# band_pass_filter.net
KiCad netlist of a schematic drawn in EAGLE
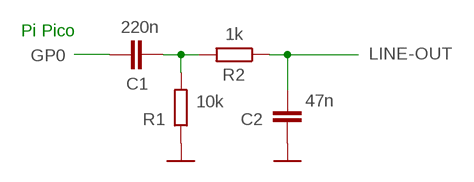
[diagram p0: schematic, sheet 1]

(export (version "E")
  (design (tool "Eeschema 10.0.6"))
  (components
    (comp (ref "C1")
      (value "220n")
      (footprint "eagle-import:C0805")
      (libsource (lib "eagle-import") (part "C"))
    )
    (comp (ref "C2")
      (value "47n")
      (footprint "eagle-import:C0805")
      (libsource (lib "eagle-import") (part "C"))
    )
    (comp (ref "R1")
      (value "10k")
      (footprint "eagle-import:R0805")
      (libsource (lib "eagle-import") (part "R"))
    )
    (comp (ref "R2")
      (value "1k")
      (footprint "eagle-import:R0805")
      (libsource (lib "eagle-import") (part "R"))
    )
  )
  (nets
    (net (code "1") (name "/GP0") (class "Default")
      (node (ref "C1") (pin "1") (pinfunction "1_1") (pintype "passive"))
    )
    (net (code "2") (name "/LINE-OUT") (class "Default")
      (node (ref "C2") (pin "2") (pinfunction "2_2") (pintype "passive"))
      (node (ref "R2") (pin "1") (pinfunction "1_1") (pintype "passive"))
    )
    (net (code "3") (name "GND") (class "Default")
      (node (ref "C2") (pin "1") (pinfunction "1_1") (pintype "passive"))
      (node (ref "R1") (pin "1") (pinfunction "1_1") (pintype "passive"))
    )
    (net (code "4") (name "Net-(C1-Pad2)") (class "Default")
      (node (ref "C1") (pin "2") (pinfunction "2_2") (pintype "passive"))
      (node (ref "R1") (pin "2") (pinfunction "2_2") (pintype "passive"))
      (node (ref "R2") (pin "2") (pinfunction "2_2") (pintype "passive"))
    )
  )
)
